# v1_0.net
KiCad netlist of a schematic drawn in Altium Designer
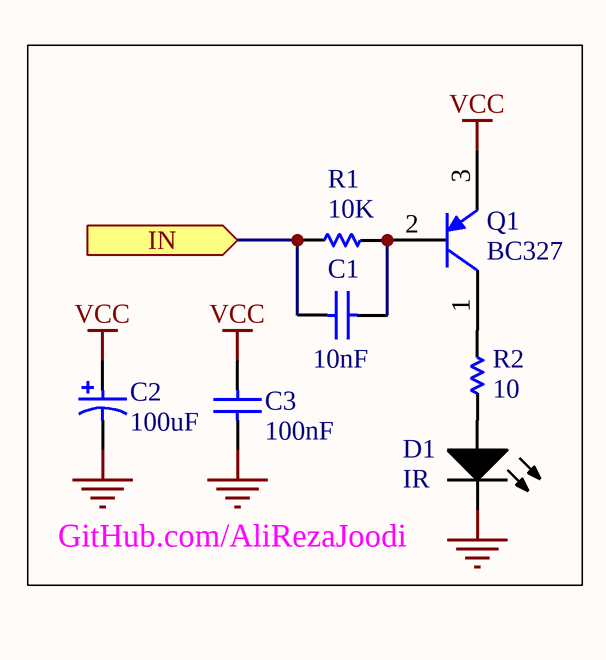
[diagram p0: v1.0.SchDoc]

(export (version "E")
  (design (tool "Eeschema 10.0.6"))
  (components
    (comp (ref "C1")
      (value "10nF")
      (footprint "C_THD_CER_(P2.54-D3.5-T1.5)")
      (description "Capacitor, Ceramic Multilayer")
      (libsource (lib "Passive") (part "Capacitor_Ceramic"))
    )
    (comp (ref "C2")
      (value "100uF")
      (footprint "C_THD_EL_(P2.54-D6-H11)")
      (description "Capacitor, Electrolytic")
      (libsource (lib "Passive") (part "Capacitor_Electrolytic"))
    )
    (comp (ref "C3")
      (value "100nF")
      (footprint "C_THD_CER_(P2.54-D3.5-T1.5)")
      (description "Capacitor, Ceramic Multilayer")
      (libsource (lib "Passive") (part "Capacitor_Ceramic"))
    )
    (comp (ref "D1")
      (value "IR")
      (footprint "LED_THD_5MM_GREEN")
      (description "LED")
      (fields (field (name "MANUFACTURER") "Generic Components") (field (name "PUBLISHER") "Altium Limited"))
      (libsource (lib "Display") (part "LED"))
    )
    (comp (ref "Q1")
      (value "BC327")
      (description "Transistor, BJT, PNP")
      (libsource (lib "Passive") (part "Transistor_BJT_PNP"))
    )
    (comp (ref "R1")
      (value "10K")
      (footprint "R_THD_AXIAL0.4(1/4W)")
      (description "Resistor")
      (libsource (lib "Passive") (part "Resistor"))
    )
    (comp (ref "R2")
      (value "10")
      (footprint "R_THD_AXIAL0.4(1/4W)")
      (description "Resistor")
      (libsource (lib "Passive") (part "Resistor"))
    )
  )
  (nets
    (net (code "1") (name "/IN") (class "Default")
      (node (ref "C1") (pin "1") (pinfunction "1_1") (pintype "passive"))
      (node (ref "R1") (pin "2") (pinfunction "2_2") (pintype "passive"))
    )
    (net (code "2") (name "GND") (class "Default")
      (node (ref "C2") (pin "2") (pinfunction "2_2") (pintype "passive"))
      (node (ref "C3") (pin "2") (pinfunction "2_2") (pintype "passive"))
      (node (ref "D1") (pin "2") (pinfunction "K_2") (pintype "passive"))
    )
    (net (code "3") (name "Net-(D1-A)") (class "Default")
      (node (ref "D1") (pin "1") (pinfunction "A_1") (pintype "passive"))
      (node (ref "R2") (pin "1") (pinfunction "1_1") (pintype "passive"))
    )
    (net (code "4") (name "Net-(Q1-B)") (class "Default")
      (node (ref "C1") (pin "2") (pinfunction "2_2") (pintype "passive"))
      (node (ref "Q1") (pin "2") (pinfunction "B_2") (pintype "passive"))
      (node (ref "R1") (pin "1") (pinfunction "1_1") (pintype "passive"))
    )
    (net (code "5") (name "Net-(Q1-C)") (class "Default")
      (node (ref "Q1") (pin "1") (pinfunction "C_1") (pintype "passive"))
      (node (ref "R2") (pin "2") (pinfunction "2_2") (pintype "passive"))
    )
    (net (code "6") (name "VCC") (class "Default")
      (node (ref "C2") (pin "1") (pinfunction "1_1") (pintype "passive"))
      (node (ref "C3") (pin "1") (pinfunction "1_1") (pintype "passive"))
      (node (ref "Q1") (pin "3") (pinfunction "E_3") (pintype "passive"))
    )
  )
)
